# ProDoc_Schematic1_2024-07-10.net
KiCad netlist of a schematic drawn in EasyEDA Pro
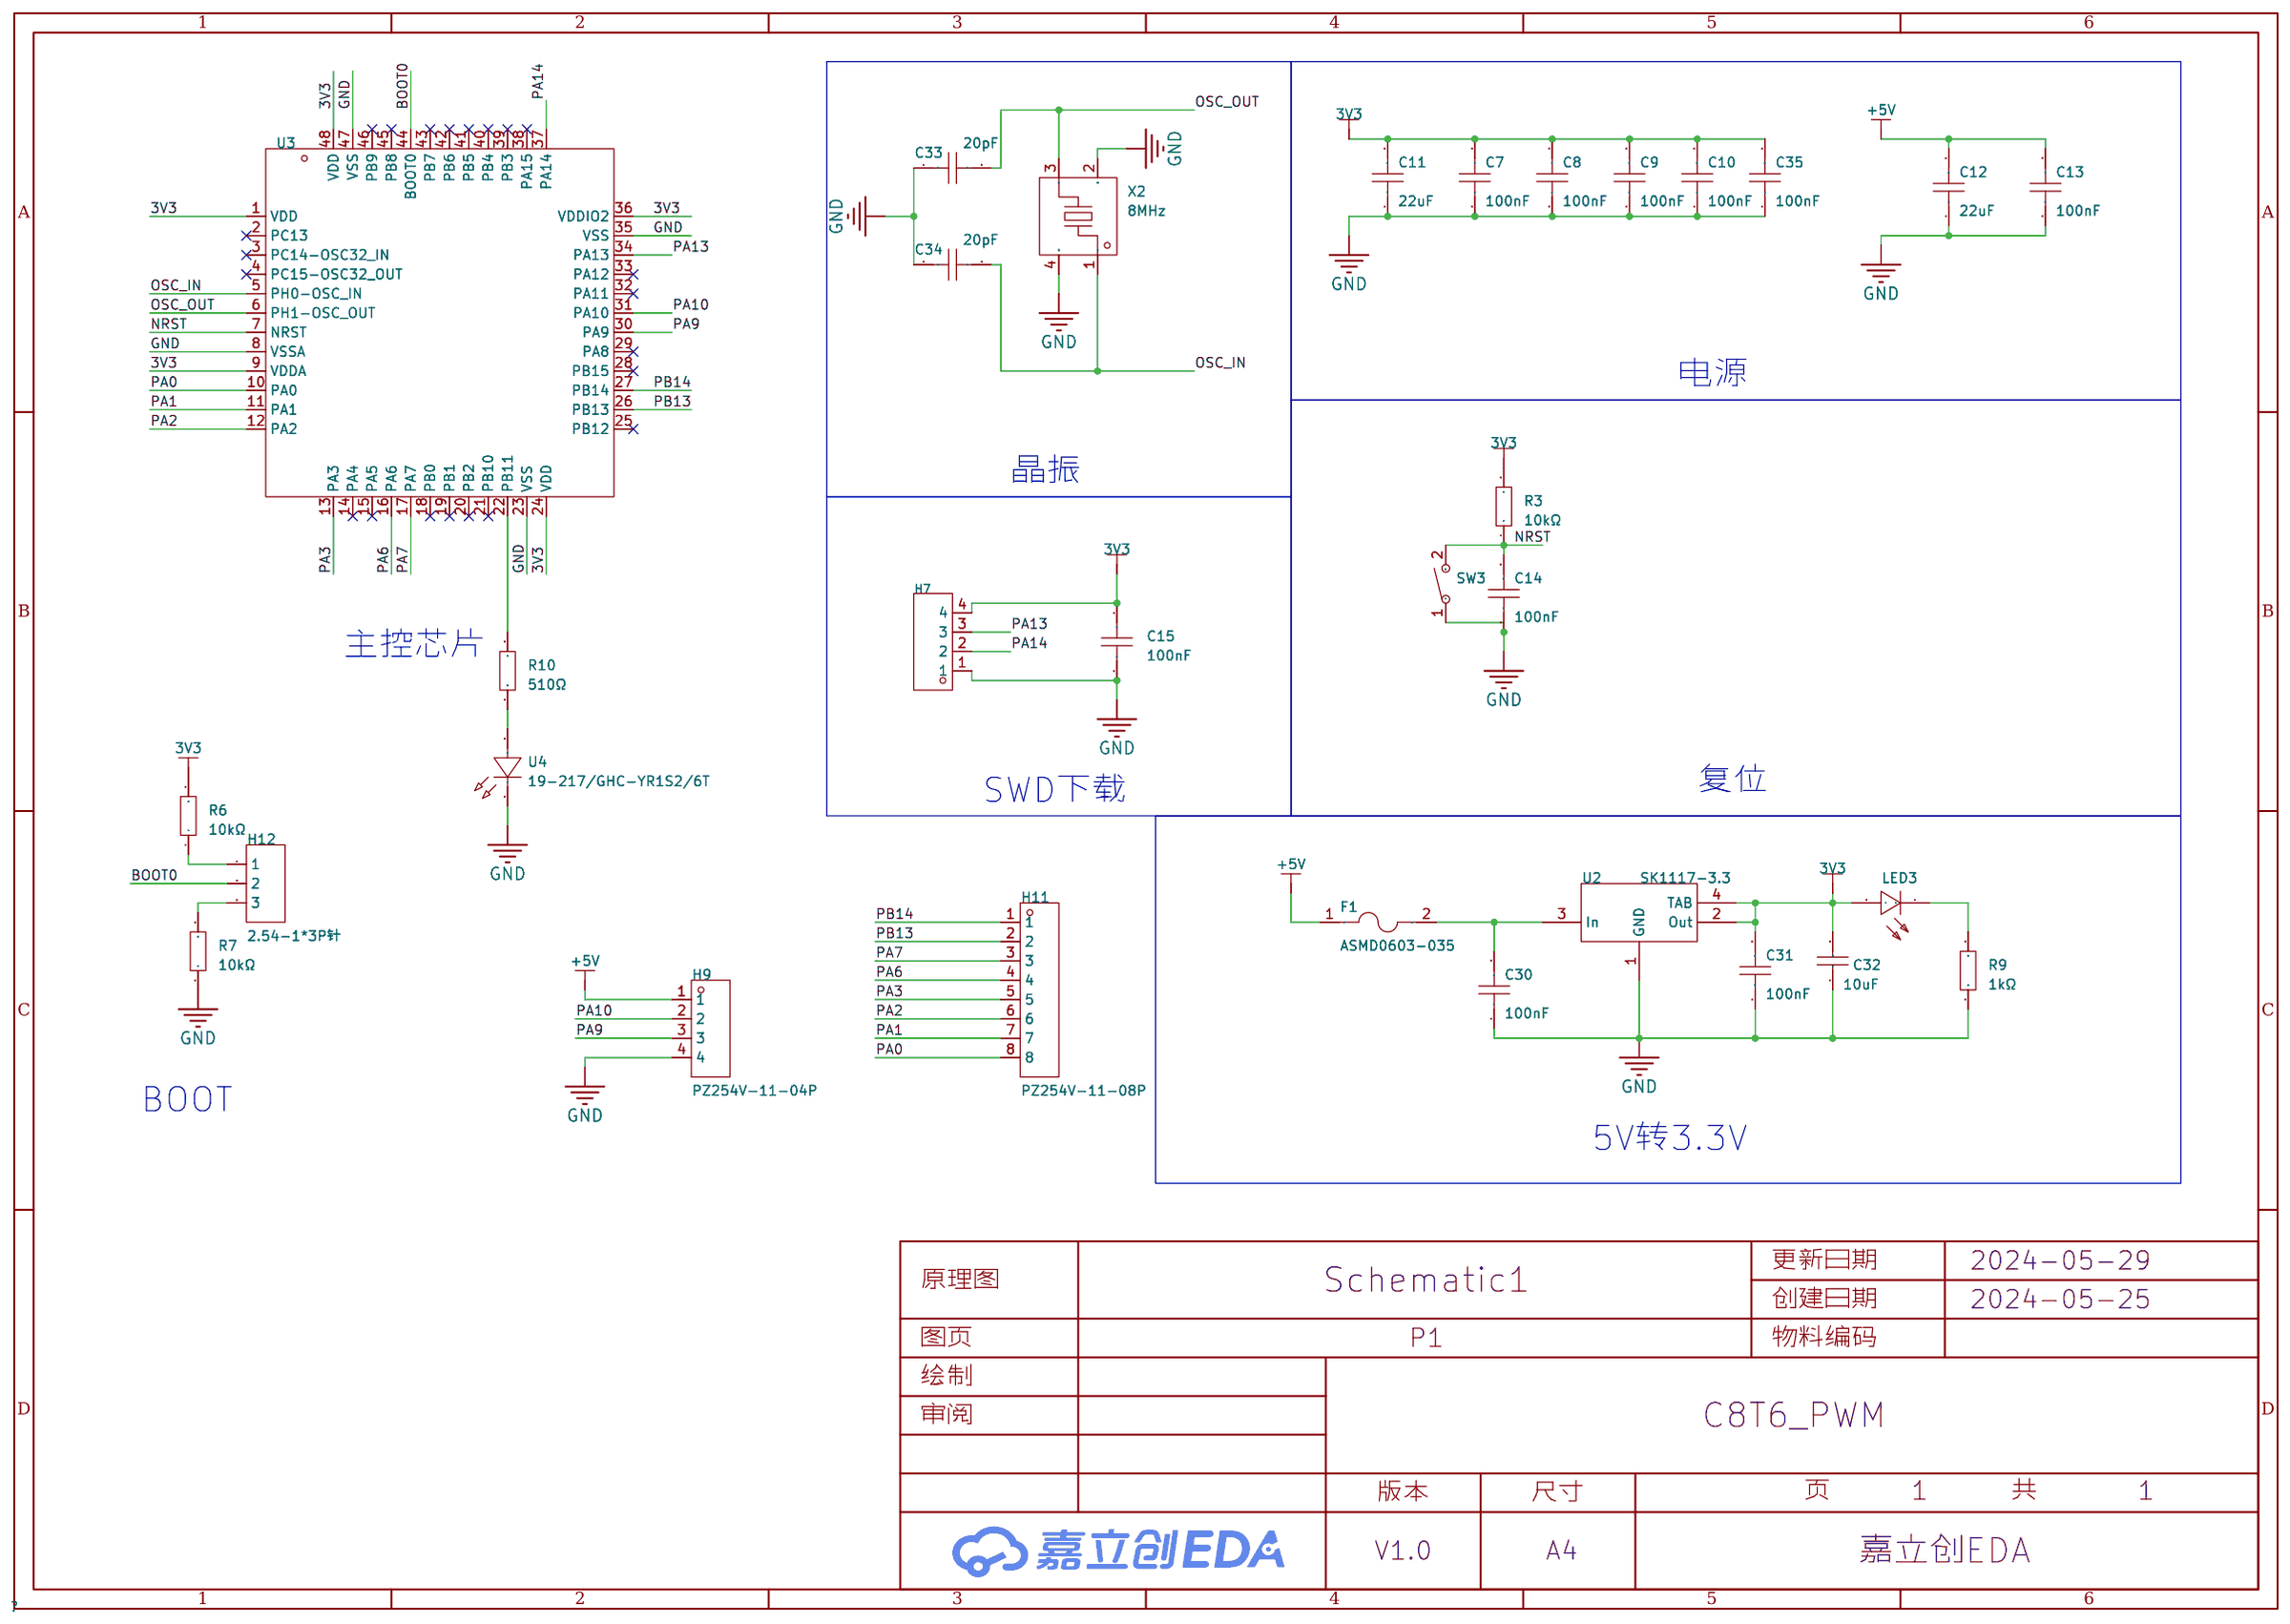
[diagram p0: schematic sheet]

(export (version "E")
  (design (tool "Eeschema 10.0.6"))
  (components
    (comp (ref "C7")
      (value "100nF")
      (footprint "easyedapro:C0603")
      (description "容值:100nF;精度:-20%~+80%;额定电压:50V;材质(温度系数):Y5V;")
      (fields (field (name "Manufacturer Part") "0603F104Z500CT") (field (name "Manufacturer") "Walsin(华新科)"))
      (libsource (lib "easyedapro") (part "0603F104Z500"))
    )
    (comp (ref "C8")
      (value "100nF")
      (footprint "easyedapro:C0603")
      (description "容值:100nF;精度:-20%~+80%;额定电压:50V;材质(温度系数):Y5V;")
      (fields (field (name "Manufacturer Part") "0603F104Z500CT") (field (name "Manufacturer") "Walsin(华新科)"))
      (libsource (lib "easyedapro") (part "0603F104Z500"))
    )
    (comp (ref "C9")
      (value "100nF")
      (footprint "easyedapro:C0603")
      (description "容值:100nF;精度:-20%~+80%;额定电压:50V;材质(温度系数):Y5V;")
      (fields (field (name "Manufacturer Part") "0603F104Z500CT") (field (name "Manufacturer") "Walsin(华新科)"))
      (libsource (lib "easyedapro") (part "0603F104Z500"))
    )
    (comp (ref "C10")
      (value "100nF")
      (footprint "easyedapro:C0603")
      (description "容值:100nF;精度:-20%~+80%;额定电压:50V;材质(温度系数):Y5V;")
      (fields (field (name "Manufacturer Part") "0603F104Z500CT") (field (name "Manufacturer") "Walsin(华新科)"))
      (libsource (lib "easyedapro") (part "0603F104Z500"))
    )
    (comp (ref "C11")
      (value "22uF")
      (footprint "easyedapro:C0603")
      (description "容值:22uF;精度:±20%;额定电压:4V;材质(温度系数):X5R;")
      (fields
        (field (name "Manufacturer Part") "CL10A226MR8NQNC")
        (field (name "Manufacturer") "SAMSUNG(三星)")
      )
      (libsource (lib "easyedapro") (part "CL10A226MR8NQNC"))
    )
    (comp (ref "C12")
      (value "22uF")
      (footprint "easyedapro:C0603")
      (description "容值:22uF;精度:±20%;额定电压:4V;材质(温度系数):X5R;")
      (fields
        (field (name "Manufacturer Part") "CL10A226MR8NQNC")
        (field (name "Manufacturer") "SAMSUNG(三星)")
      )
      (libsource (lib "easyedapro") (part "CL10A226MR8NQNC"))
    )
    (comp (ref "C13")
      (value "100nF")
      (footprint "easyedapro:C0603")
      (description "容值:100nF;精度:-20%~+80%;额定电压:50V;材质(温度系数):Y5V;")
      (fields (field (name "Manufacturer Part") "0603F104Z500CT") (field (name "Manufacturer") "Walsin(华新科)"))
      (libsource (lib "easyedapro") (part "0603F104Z500"))
    )
    (comp (ref "C14")
      (value "100nF")
      (footprint "easyedapro:C0603")
      (description "容值:100nF;精度:-20%~+80%;额定电压:50V;材质(温度系数):Y5V;")
      (fields (field (name "Manufacturer Part") "0603F104Z500CT") (field (name "Manufacturer") "Walsin(华新科)"))
      (libsource (lib "easyedapro") (part "0603F104Z500"))
    )
    (comp (ref "C15")
      (value "100nF")
      (footprint "easyedapro:C0603")
      (description "容值:100nF;精度:-20%~+80%;额定电压:50V;材质(温度系数):Y5V;")
      (fields (field (name "Manufacturer Part") "0603F104Z500CT") (field (name "Manufacturer") "Walsin(华新科)"))
      (libsource (lib "easyedapro") (part "0603F104Z500"))
    )
    (comp (ref "C30")
      (value "100nF")
      (footprint "easyedapro:C0603")
      (description "容值:100nF;精度:-20%~+80%;额定电压:50V;材质(温度系数):Y5V;")
      (fields (field (name "Manufacturer Part") "0603F104Z500CT") (field (name "Manufacturer") "Walsin(华新科)"))
      (libsource (lib "easyedapro") (part "0603F104Z500"))
    )
    (comp (ref "C31")
      (value "100nF")
      (footprint "easyedapro:C0603")
      (description "容值:100nF;精度:-20%~+80%;额定电压:50V;材质(温度系数):Y5V;")
      (fields (field (name "Manufacturer Part") "0603F104Z500CT") (field (name "Manufacturer") "Walsin(华新科)"))
      (libsource (lib "easyedapro") (part "0603F104Z500"))
    )
    (comp (ref "C32")
      (value "10uF")
      (footprint "easyedapro:C0805")
      (description "容值:10uF;精度:±10%;额定电压:25V;材质(温度系数):X5R;")
      (fields
        (field (name "Manufacturer Part") "CL21A106KAYNNNE")
        (field (name "Manufacturer") "SAMSUNG(三星)")
      )
      (libsource (lib "easyedapro") (part "CL21A106KAYNNNE"))
    )
    (comp (ref "C33")
      (value "20pF")
      (footprint "easyedapro:C0603")
      (description "容值:20pF;精度:±5%;额定电压:50V;材质(温度系数):C0G;")
      (fields (field (name "Manufacturer Part") "0603CG200J500NT") (field (name "Manufacturer") "FH(风华)"))
      (libsource (lib "easyedapro") (part "0603CG200J500NT"))
    )
    (comp (ref "C34")
      (value "20pF")
      (footprint "easyedapro:C0603")
      (description "容值:20pF;精度:±5%;额定电压:50V;材质(温度系数):C0G;")
      (fields (field (name "Manufacturer Part") "0603CG200J500NT") (field (name "Manufacturer") "FH(风华)"))
      (libsource (lib "easyedapro") (part "0603CG200J500NT"))
    )
    (comp (ref "C35")
      (value "100nF")
      (footprint "easyedapro:C0603")
      (description "容值:100nF;精度:-20%~+80%;额定电压:50V;材质(温度系数):Y5V;")
      (fields (field (name "Manufacturer Part") "0603F104Z500CT") (field (name "Manufacturer") "Walsin(华新科)"))
      (libsource (lib "easyedapro") (part "0603F104Z500"))
    )
    (comp (ref "F1")
      (value "ASMD0603-035")
      (footprint "easyedapro:F0603")
      (description "最大电压:6V;最大电流:40A;保持电流:350mA;跳闸电流:750mA;")
      (fields (field (name "Manufacturer") "JDTfuse(集电通)"))
      (libsource (lib "easyedapro") (part "ASMD0603-035"))
    )
    (comp (ref "H7")
      (value "2.54-1*4P反弯排针")
      (footprint "easyedapro:HDR-TH_4P-P2.54-H-M-W10.4")
      (fields (field (name "Manufacturer") "BOOMELE(博穆精密)"))
      (libsource (lib "easyedapro") (part "2.54-1*4P反弯排针"))
    )
    (comp (ref "H9")
      (value "PZ254V-11-04P")
      (footprint "easyedapro:HDR-TH_4P-P2.54-V-M")
      (fields (field (name "Manufacturer") "XFCN(兴飞)"))
      (libsource (lib "easyedapro") (part "PZ254V-11-04P_C2691448"))
    )
    (comp (ref "H11")
      (value "PZ254V-11-08P")
      (footprint "easyedapro:HDR-TH_8P-P2.54-V-M")
      (fields (field (name "Manufacturer") "XFCN(兴飞)"))
      (libsource (lib "easyedapro") (part "PZ254V-11-08P"))
    )
    (comp (ref "H12")
      (value "2.54-1*3P针")
      (footprint "easyedapro:HDR-TH_3P-P2.54-V-M-1")
      (fields (field (name "Manufacturer") "BOOMELE(博穆精密)"))
      (libsource (lib "easyedapro") (part "Header-Male-2.54_1x3"))
    )
    (comp (ref "LED3")
      (value "NCD0603R1")
      (footprint "easyedapro:LED0603-RD_RED")
      (description "发光颜色:红灯;")
      (fields (field (name "Manufacturer") "国星光电"))
      (libsource (lib "easyedapro") (part "FC-DA1608HRK-620D"))
    )
    (comp (ref "R3")
      (value "10kΩ")
      (footprint "easyedapro:R0805")
      (description "电阻类型:厚膜电阻;阻值:10kΩ;精度:±1%;功率:125mW;")
      (fields
        (field (name "Manufacturer Part") "0805W8F1002T5E")
        (field (name "Manufacturer") "UNI-ROYAL(厚声)")
      )
      (libsource (lib "easyedapro") (part "0805W8F1002T5E"))
    )
    (comp (ref "R6")
      (value "10kΩ")
      (footprint "easyedapro:R0603")
      (description "电阻类型:厚膜电阻;阻值:10kΩ;精度:±1%;功率:100mW;最大工作电压:75V;温度系数:±100ppm/°C;")
      (fields
        (field (name "Manufacturer Part") "0603WAF1002T5E")
        (field (name "Manufacturer") "UNI-ROYAL(厚声)")
      )
      (libsource (lib "easyedapro") (part "0603WAF1002T5E"))
    )
    (comp (ref "R7")
      (value "10kΩ")
      (footprint "easyedapro:R0603")
      (description "电阻类型:厚膜电阻;阻值:10kΩ;精度:±1%;功率:100mW;最大工作电压:75V;温度系数:±100ppm/°C;")
      (fields
        (field (name "Manufacturer Part") "0603WAF1002T5E")
        (field (name "Manufacturer") "UNI-ROYAL(厚声)")
      )
      (libsource (lib "easyedapro") (part "0603WAF1002T5E"))
    )
    (comp (ref "R9")
      (value "1kΩ")
      (footprint "easyedapro:R0805")
      (description "电阻类型:厚膜电阻;阻值:1kΩ;精度:±1%;功率:125mW;")
      (fields
        (field (name "Manufacturer Part") "0805W8F1001T5E")
        (field (name "Manufacturer") "UNI-ROYAL(厚声)")
      )
      (libsource (lib "easyedapro") (part "0805W8F1001T5E"))
    )
    (comp (ref "R10")
      (value "510Ω")
      (footprint "easyedapro:R0603")
      (description "电阻类型:厚膜电阻;阻值:510Ω;精度:±1%;功率:100mW;最大工作电压:75V;温度系数:±100ppm/°C;")
      (fields
        (field (name "Manufacturer Part") "0603WAF5100T5E")
        (field (name "Manufacturer") "UNI-ROYAL(厚声)")
      )
      (libsource (lib "easyedapro") (part "0603WAF5100T5E"))
    )
    (comp (ref "SW3")
      (value "UK-B0205G43-DP25Y")
      (footprint "easyedapro:KEY-TH_L6.0-W3.5-P6.50")
      (description "触点电流:50mA;额定电压(DC):12V;绝缘电阻:100MΩ;电路结构:单刀单掷;安装方式:直插;带灯:无;作用力:250gf@±30gf;机械寿命:10万次;带支架:否;")
      (fields (field (name "Manufacturer") "USAKRO(美韩)"))
      (libsource (lib "easyedapro") (part "UK-B0205G43-DP25Y"))
    )
    (comp (ref "U2")
      (value "SK1117-3.3")
      (footprint "easyedapro:SOT-223_L6.5-W3.5-P2.30-LS7.0-BR")
      (description "输出类型:固定;输出极性:正;最大输入电压:18V;输出电压:3.3V;输出电流:-;电源纹波抑制比(PSRR):70dB@(120Hz);")
      (fields (field (name "Manufacturer") "SHIKUES(时科)"))
      (libsource (lib "easyedapro") (part "AMS1117-3.3_C165482"))
    )
    (comp (ref "U3")
      (value "STM32L051C8T6")
      (footprint "easyedapro:LQFP-48_L7.0-W7.0-P0.50-LS9.0-BL")
      (description "CPU内核:ARM-M系列;程序存储容量:64KB;RAM总容量:8KB;GPIO端口数量:37;工作电压范围:1.65V~3.6V;CPU最大主频:32MHz;程序存储器类型:FLASH;")
      (fields (field (name "Manufacturer") "ST(意法半导体)"))
      (libsource (lib "easyedapro") (part "STM32L051C8T6"))
    )
    (comp (ref "U4")
      (value "19-217/GHC-YR1S2/6T")
      (footprint "easyedapro:LED0603-RD_GREEN")
      (fields (field (name "Manufacturer") "EVERLIGHT(亿光)"))
      (libsource (lib "easyedapro") (part "19-217/GHC-YR1S2/6T"))
    )
    (comp (ref "X2")
      (value "8MHz")
      (footprint "easyedapro:OSC-SMD_4P-L3.2-W2.5-BL")
      (description "晶振类型:贴片晶振;频率:8MHz;常温频差:±10ppm;外接负载电容:12pF;频率稳定度(全温):±20ppm;")
      (fields (field (name "Manufacturer Part") "X32258MOB4SI") (field (name "Manufacturer") "YXC(扬兴晶振)"))
      (libsource (lib "easyedapro") (part "X32258MOB4SI"))
    )
  )
  (nets
    (net (code "1") (name "+5V") (class "Default")
      (node (ref "C12") (pin "2") (pinfunction "2_2") (pintype "input"))
      (node (ref "C13") (pin "2") (pinfunction "2_2") (pintype "input"))
      (node (ref "F1") (pin "1") (pinfunction "1_1") (pintype "input"))
      (node (ref "H9") (pin "1") (pinfunction "1_1") (pintype "unspecified"))
    )
    (net (code "2") (name "/BOOT0") (class "Default")
      (node (ref "H12") (pin "2") (pinfunction "2_2") (pintype "input"))
      (node (ref "U3") (pin "44") (pinfunction "BOOT0_44") (pintype "unspecified"))
    )
    (net (code "3") (name "/NRST") (class "Default")
      (node (ref "C14") (pin "2") (pinfunction "2_2") (pintype "input"))
      (node (ref "R3") (pin "1") (pinfunction "1_1") (pintype "input"))
      (node (ref "SW3") (pin "2") (pinfunction "2_2") (pintype "input"))
      (node (ref "U3") (pin "7") (pinfunction "NRST_7") (pintype "unspecified"))
    )
    (net (code "4") (name "/OSC_IN") (class "Default")
      (node (ref "C34") (pin "2") (pinfunction "2_2") (pintype "unspecified"))
      (node (ref "U3") (pin "5") (pinfunction "PH0-OSC_IN_5") (pintype "unspecified"))
      (node (ref "X2") (pin "1") (pinfunction "1_1") (pintype "input"))
    )
    (net (code "5") (name "/OSC_OUT") (class "Default")
      (node (ref "C33") (pin "2") (pinfunction "2_2") (pintype "unspecified"))
      (node (ref "U3") (pin "6") (pinfunction "PH1-OSC_OUT_6") (pintype "unspecified"))
      (node (ref "X2") (pin "3") (pinfunction "3_3") (pintype "input"))
    )
    (net (code "6") (name "/PA0") (class "Default")
      (node (ref "H11") (pin "8") (pinfunction "8_8") (pintype "unspecified"))
      (node (ref "U3") (pin "10") (pinfunction "PA0_10") (pintype "unspecified"))
    )
    (net (code "7") (name "/PA1") (class "Default")
      (node (ref "H11") (pin "7") (pinfunction "7_7") (pintype "unspecified"))
      (node (ref "U3") (pin "11") (pinfunction "PA1_11") (pintype "unspecified"))
    )
    (net (code "8") (name "/PA2") (class "Default")
      (node (ref "H11") (pin "6") (pinfunction "6_6") (pintype "unspecified"))
      (node (ref "U3") (pin "12") (pinfunction "PA2_12") (pintype "unspecified"))
    )
    (net (code "9") (name "/PA3") (class "Default")
      (node (ref "H11") (pin "5") (pinfunction "5_5") (pintype "unspecified"))
      (node (ref "U3") (pin "13") (pinfunction "PA3_13") (pintype "unspecified"))
    )
    (net (code "10") (name "/PA6") (class "Default")
      (node (ref "H11") (pin "4") (pinfunction "4_4") (pintype "unspecified"))
      (node (ref "U3") (pin "16") (pinfunction "PA6_16") (pintype "unspecified"))
    )
    (net (code "11") (name "/PA7") (class "Default")
      (node (ref "H11") (pin "3") (pinfunction "3_3") (pintype "unspecified"))
      (node (ref "U3") (pin "17") (pinfunction "PA7_17") (pintype "unspecified"))
    )
    (net (code "12") (name "/PA9") (class "Default")
      (node (ref "H9") (pin "3") (pinfunction "3_3") (pintype "unspecified"))
      (node (ref "U3") (pin "30") (pinfunction "PA9_30") (pintype "unspecified"))
    )
    (net (code "13") (name "/PA10") (class "Default")
      (node (ref "H9") (pin "2") (pinfunction "2_2") (pintype "unspecified"))
      (node (ref "U3") (pin "31") (pinfunction "PA10_31") (pintype "unspecified"))
    )
    (net (code "14") (name "/PA13") (class "Default")
      (node (ref "H7") (pin "3") (pinfunction "3_3") (pintype "input"))
      (node (ref "U3") (pin "34") (pinfunction "PA13_34") (pintype "unspecified"))
    )
    (net (code "15") (name "/PA14") (class "Default")
      (node (ref "H7") (pin "2") (pinfunction "2_2") (pintype "input"))
      (node (ref "U3") (pin "37") (pinfunction "PA14_37") (pintype "unspecified"))
    )
    (net (code "16") (name "/PB13") (class "Default")
      (node (ref "H11") (pin "2") (pinfunction "2_2") (pintype "unspecified"))
      (node (ref "U3") (pin "26") (pinfunction "PB13_26") (pintype "unspecified"))
    )
    (net (code "17") (name "/PB14") (class "Default")
      (node (ref "H11") (pin "1") (pinfunction "1_1") (pintype "unspecified"))
      (node (ref "U3") (pin "27") (pinfunction "PB14_27") (pintype "unspecified"))
    )
    (net (code "18") (name "3V3") (class "Default")
      (node (ref "C10") (pin "2") (pinfunction "2_2") (pintype "input"))
      (node (ref "C11") (pin "2") (pinfunction "2_2") (pintype "input"))
      (node (ref "C15") (pin "1") (pinfunction "1_1") (pintype "input"))
      (node (ref "C31") (pin "2") (pinfunction "2_2") (pintype "input"))
      (node (ref "C32") (pin "2") (pinfunction "2_2") (pintype "input"))
      (node (ref "C35") (pin "2") (pinfunction "2_2") (pintype "input"))
      (node (ref "C7") (pin "2") (pinfunction "2_2") (pintype "input"))
      (node (ref "C8") (pin "2") (pinfunction "2_2") (pintype "input"))
      (node (ref "C9") (pin "2") (pinfunction "2_2") (pintype "input"))
      (node (ref "H7") (pin "4") (pinfunction "4_4") (pintype "input"))
      (node (ref "LED3") (pin "2") (pinfunction "A_2") (pintype "input"))
      (node (ref "R3") (pin "2") (pinfunction "2_2") (pintype "input"))
      (node (ref "R6") (pin "2") (pinfunction "2_2") (pintype "input"))
      (node (ref "U2") (pin "2") (pinfunction "Out_2") (pintype "input"))
      (node (ref "U2") (pin "4") (pinfunction "TAB_4") (pintype "input"))
      (node (ref "U3") (pin "1") (pinfunction "VDD_1") (pintype "unspecified"))
      (node (ref "U3") (pin "24") (pinfunction "VDD_24") (pintype "unspecified"))
      (node (ref "U3") (pin "36") (pinfunction "VDDIO2_36") (pintype "unspecified"))
      (node (ref "U3") (pin "48") (pinfunction "VDD_48") (pintype "unspecified"))
      (node (ref "U3") (pin "9") (pinfunction "VDDA_9") (pintype "unspecified"))
    )
    (net (code "19") (name "GND") (class "Default")
      (node (ref "C10") (pin "1") (pinfunction "1_1") (pintype "input"))
      (node (ref "C11") (pin "1") (pinfunction "1_1") (pintype "input"))
      (node (ref "C12") (pin "1") (pinfunction "1_1") (pintype "input"))
      (node (ref "C13") (pin "1") (pinfunction "1_1") (pintype "input"))
      (node (ref "C14") (pin "1") (pinfunction "1_1") (pintype "input"))
      (node (ref "C15") (pin "2") (pinfunction "2_2") (pintype "input"))
      (node (ref "C30") (pin "1") (pinfunction "1_1") (pintype "input"))
      (node (ref "C31") (pin "1") (pinfunction "1_1") (pintype "input"))
      (node (ref "C32") (pin "1") (pinfunction "1_1") (pintype "input"))
      (node (ref "C33") (pin "1") (pinfunction "1_1") (pintype "unspecified"))
      (node (ref "C34") (pin "1") (pinfunction "1_1") (pintype "unspecified"))
      (node (ref "C35") (pin "1") (pinfunction "1_1") (pintype "input"))
      (node (ref "C7") (pin "1") (pinfunction "1_1") (pintype "input"))
      (node (ref "C8") (pin "1") (pinfunction "1_1") (pintype "input"))
      (node (ref "C9") (pin "1") (pinfunction "1_1") (pintype "input"))
      (node (ref "H7") (pin "1") (pinfunction "1_1") (pintype "input"))
      (node (ref "H9") (pin "4") (pinfunction "4_4") (pintype "unspecified"))
      (node (ref "R7") (pin "1") (pinfunction "1_1") (pintype "input"))
      (node (ref "R9") (pin "1") (pinfunction "1_1") (pintype "input"))
      (node (ref "SW3") (pin "1") (pinfunction "1_1") (pintype "input"))
      (node (ref "U2") (pin "1") (pinfunction "GND_1") (pintype "input"))
      (node (ref "U3") (pin "23") (pinfunction "VSS_23") (pintype "unspecified"))
      (node (ref "U3") (pin "35") (pinfunction "VSS_35") (pintype "unspecified"))
      (node (ref "U3") (pin "47") (pinfunction "VSS_47") (pintype "unspecified"))
      (node (ref "U3") (pin "8") (pinfunction "VSSA_8") (pintype "unspecified"))
      (node (ref "U4") (pin "1") (pinfunction "K_1") (pintype "unspecified"))
      (node (ref "X2") (pin "2") (pinfunction "GND_2") (pintype "input"))
      (node (ref "X2") (pin "4") (pinfunction "GND_4") (pintype "input"))
    )
    (net (code "20") (name "Net-(H12-Pad1)") (class "Default")
      (node (ref "H12") (pin "1") (pinfunction "1_1") (pintype "input"))
      (node (ref "R6") (pin "1") (pinfunction "1_1") (pintype "input"))
    )
    (net (code "21") (name "Net-(H12-Pad3)") (class "Default")
      (node (ref "H12") (pin "3") (pinfunction "3_3") (pintype "input"))
      (node (ref "R7") (pin "2") (pinfunction "2_2") (pintype "input"))
    )
    (net (code "22") (name "Net-(LED3-K)") (class "Default")
      (node (ref "LED3") (pin "1") (pinfunction "K_1") (pintype "input"))
      (node (ref "R9") (pin "2") (pinfunction "2_2") (pintype "input"))
    )
    (net (code "23") (name "Net-(U2-In)") (class "Default")
      (node (ref "C30") (pin "2") (pinfunction "2_2") (pintype "input"))
      (node (ref "F1") (pin "2") (pinfunction "2_2") (pintype "input"))
      (node (ref "U2") (pin "3") (pinfunction "In_3") (pintype "input"))
    )
    (net (code "24") (name "Net-(U3-PB11)") (class "Default")
      (node (ref "R10") (pin "2") (pinfunction "2_2") (pintype "input"))
      (node (ref "U3") (pin "22") (pinfunction "PB11_22") (pintype "unspecified"))
    )
    (net (code "25") (name "Net-(U4-A)") (class "Default")
      (node (ref "R10") (pin "1") (pinfunction "1_1") (pintype "input"))
      (node (ref "U4") (pin "2") (pinfunction "A_2") (pintype "unspecified"))
    )
    (net (code "26") (name "unconnected-(U3-PA4-Pad14)") (class "Default")
      (node (ref "U3") (pin "14") (pinfunction "PA4_14") (pintype "unspecified+no_connect"))
    )
    (net (code "27") (name "unconnected-(U3-PA5-Pad15)") (class "Default")
      (node (ref "U3") (pin "15") (pinfunction "PA5_15") (pintype "unspecified+no_connect"))
    )
    (net (code "28") (name "unconnected-(U3-PA8-Pad29)") (class "Default")
      (node (ref "U3") (pin "29") (pinfunction "PA8_29") (pintype "unspecified+no_connect"))
    )
    (net (code "29") (name "unconnected-(U3-PA11-Pad32)") (class "Default")
      (node (ref "U3") (pin "32") (pinfunction "PA11_32") (pintype "unspecified+no_connect"))
    )
    (net (code "30") (name "unconnected-(U3-PA12-Pad33)") (class "Default")
      (node (ref "U3") (pin "33") (pinfunction "PA12_33") (pintype "unspecified+no_connect"))
    )
    (net (code "31") (name "unconnected-(U3-PA15-Pad38)") (class "Default")
      (node (ref "U3") (pin "38") (pinfunction "PA15_38") (pintype "unspecified+no_connect"))
    )
    (net (code "32") (name "unconnected-(U3-PB0-Pad18)") (class "Default")
      (node (ref "U3") (pin "18") (pinfunction "PB0_18") (pintype "unspecified+no_connect"))
    )
    (net (code "33") (name "unconnected-(U3-PB1-Pad19)") (class "Default")
      (node (ref "U3") (pin "19") (pinfunction "PB1_19") (pintype "unspecified+no_connect"))
    )
    (net (code "34") (name "unconnected-(U3-PB2-Pad20)") (class "Default")
      (node (ref "U3") (pin "20") (pinfunction "PB2_20") (pintype "unspecified+no_connect"))
    )
    (net (code "35") (name "unconnected-(U3-PB3-Pad39)") (class "Default")
      (node (ref "U3") (pin "39") (pinfunction "PB3_39") (pintype "unspecified+no_connect"))
    )
    (net (code "36") (name "unconnected-(U3-PB4-Pad40)") (class "Default")
      (node (ref "U3") (pin "40") (pinfunction "PB4_40") (pintype "unspecified+no_connect"))
    )
    (net (code "37") (name "unconnected-(U3-PB5-Pad41)") (class "Default")
      (node (ref "U3") (pin "41") (pinfunction "PB5_41") (pintype "unspecified+no_connect"))
    )
    (net (code "38") (name "unconnected-(U3-PB6-Pad42)") (class "Default")
      (node (ref "U3") (pin "42") (pinfunction "PB6_42") (pintype "unspecified+no_connect"))
    )
    (net (code "39") (name "unconnected-(U3-PB7-Pad43)") (class "Default")
      (node (ref "U3") (pin "43") (pinfunction "PB7_43") (pintype "unspecified+no_connect"))
    )
    (net (code "40") (name "unconnected-(U3-PB8-Pad45)") (class "Default")
      (node (ref "U3") (pin "45") (pinfunction "PB8_45") (pintype "unspecified+no_connect"))
    )
    (net (code "41") (name "unconnected-(U3-PB9-Pad46)") (class "Default")
      (node (ref "U3") (pin "46") (pinfunction "PB9_46") (pintype "unspecified+no_connect"))
    )
    (net (code "42") (name "unconnected-(U3-PB10-Pad21)") (class "Default")
      (node (ref "U3") (pin "21") (pinfunction "PB10_21") (pintype "unspecified+no_connect"))
    )
    (net (code "43") (name "unconnected-(U3-PB12-Pad25)") (class "Default")
      (node (ref "U3") (pin "25") (pinfunction "PB12_25") (pintype "unspecified+no_connect"))
    )
    (net (code "44") (name "unconnected-(U3-PB15-Pad28)") (class "Default")
      (node (ref "U3") (pin "28") (pinfunction "PB15_28") (pintype "unspecified+no_connect"))
    )
    (net (code "45") (name "unconnected-(U3-PC13-Pad2)") (class "Default")
      (node (ref "U3") (pin "2") (pinfunction "PC13_2") (pintype "unspecified+no_connect"))
    )
    (net (code "46") (name "unconnected-(U3-PC14-OSC32_IN-Pad3)") (class "Default")
      (node (ref "U3") (pin "3") (pinfunction "PC14-OSC32_IN_3") (pintype "unspecified+no_connect"))
    )
    (net (code "47") (name "unconnected-(U3-PC15-OSC32_OUT-Pad4)") (class "Default")
      (node (ref "U3") (pin "4") (pinfunction "PC15-OSC32_OUT_4") (pintype "unspecified+no_connect"))
    )
  )
)
